# cec-wifi-bridge-rev-a.net
KiCad netlist of a schematic drawn in EAGLE
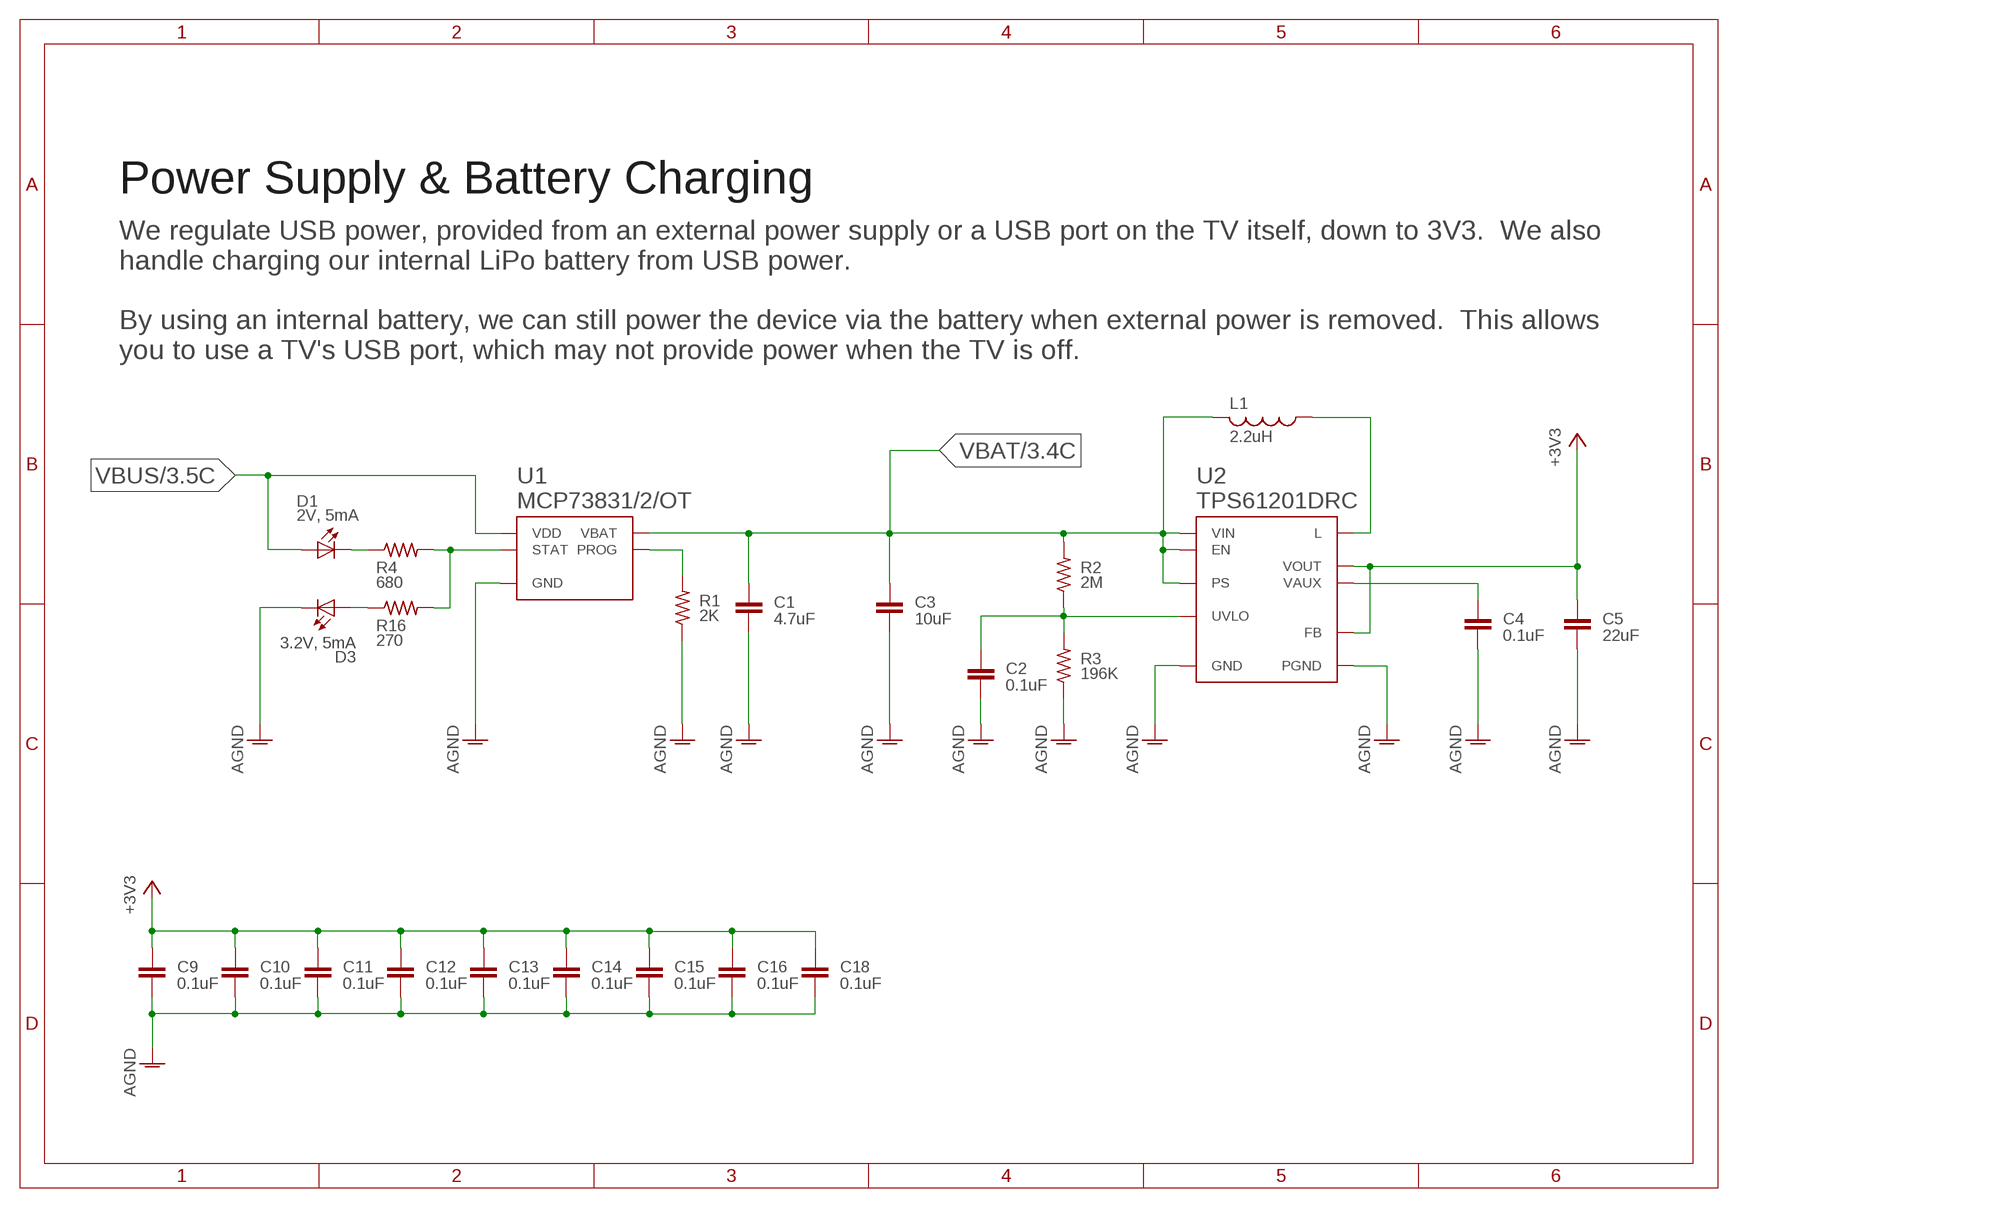
[diagram p0: schematic, sheet 1]
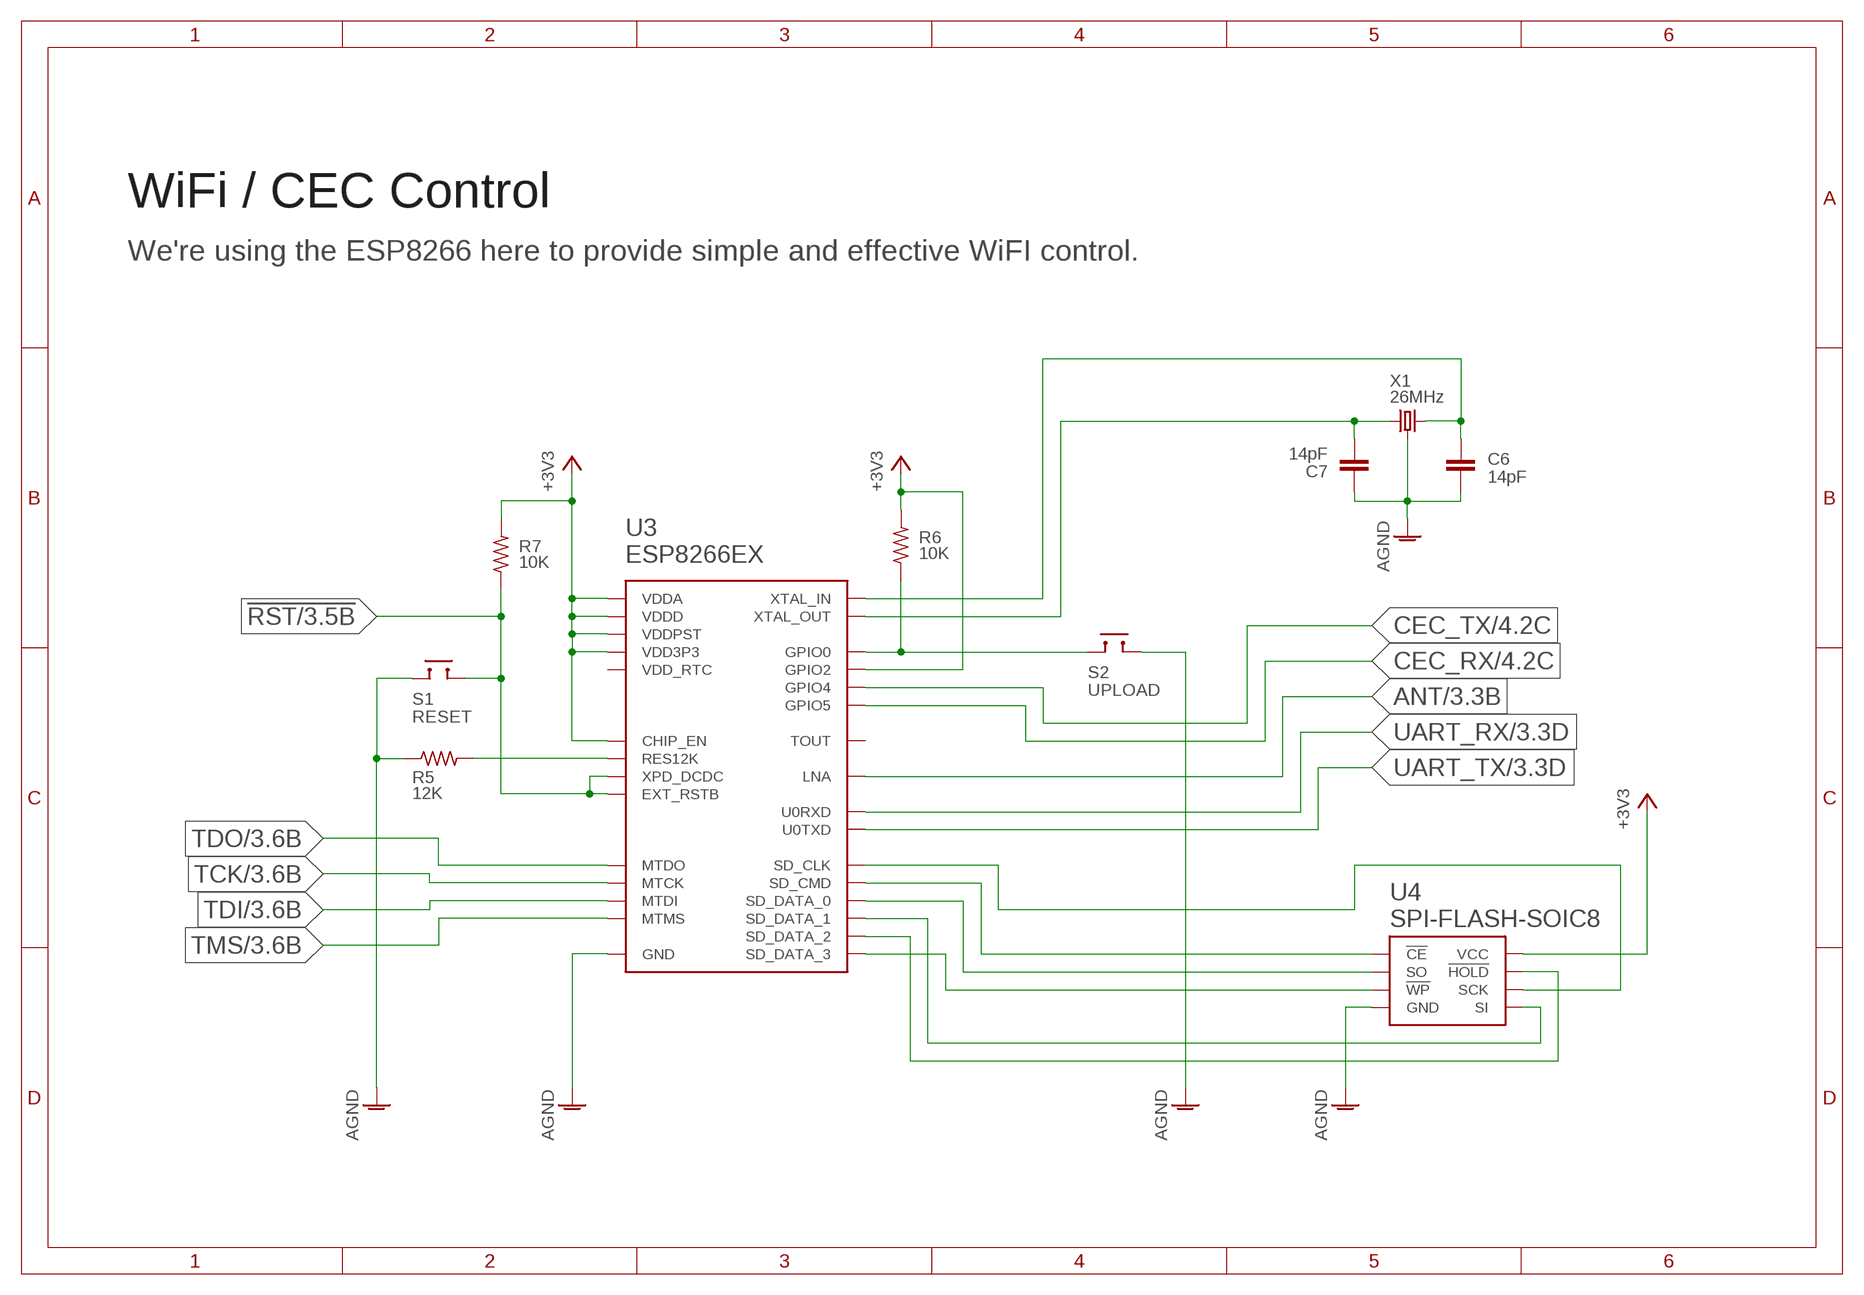
[diagram p1: schematic, sheet 2]
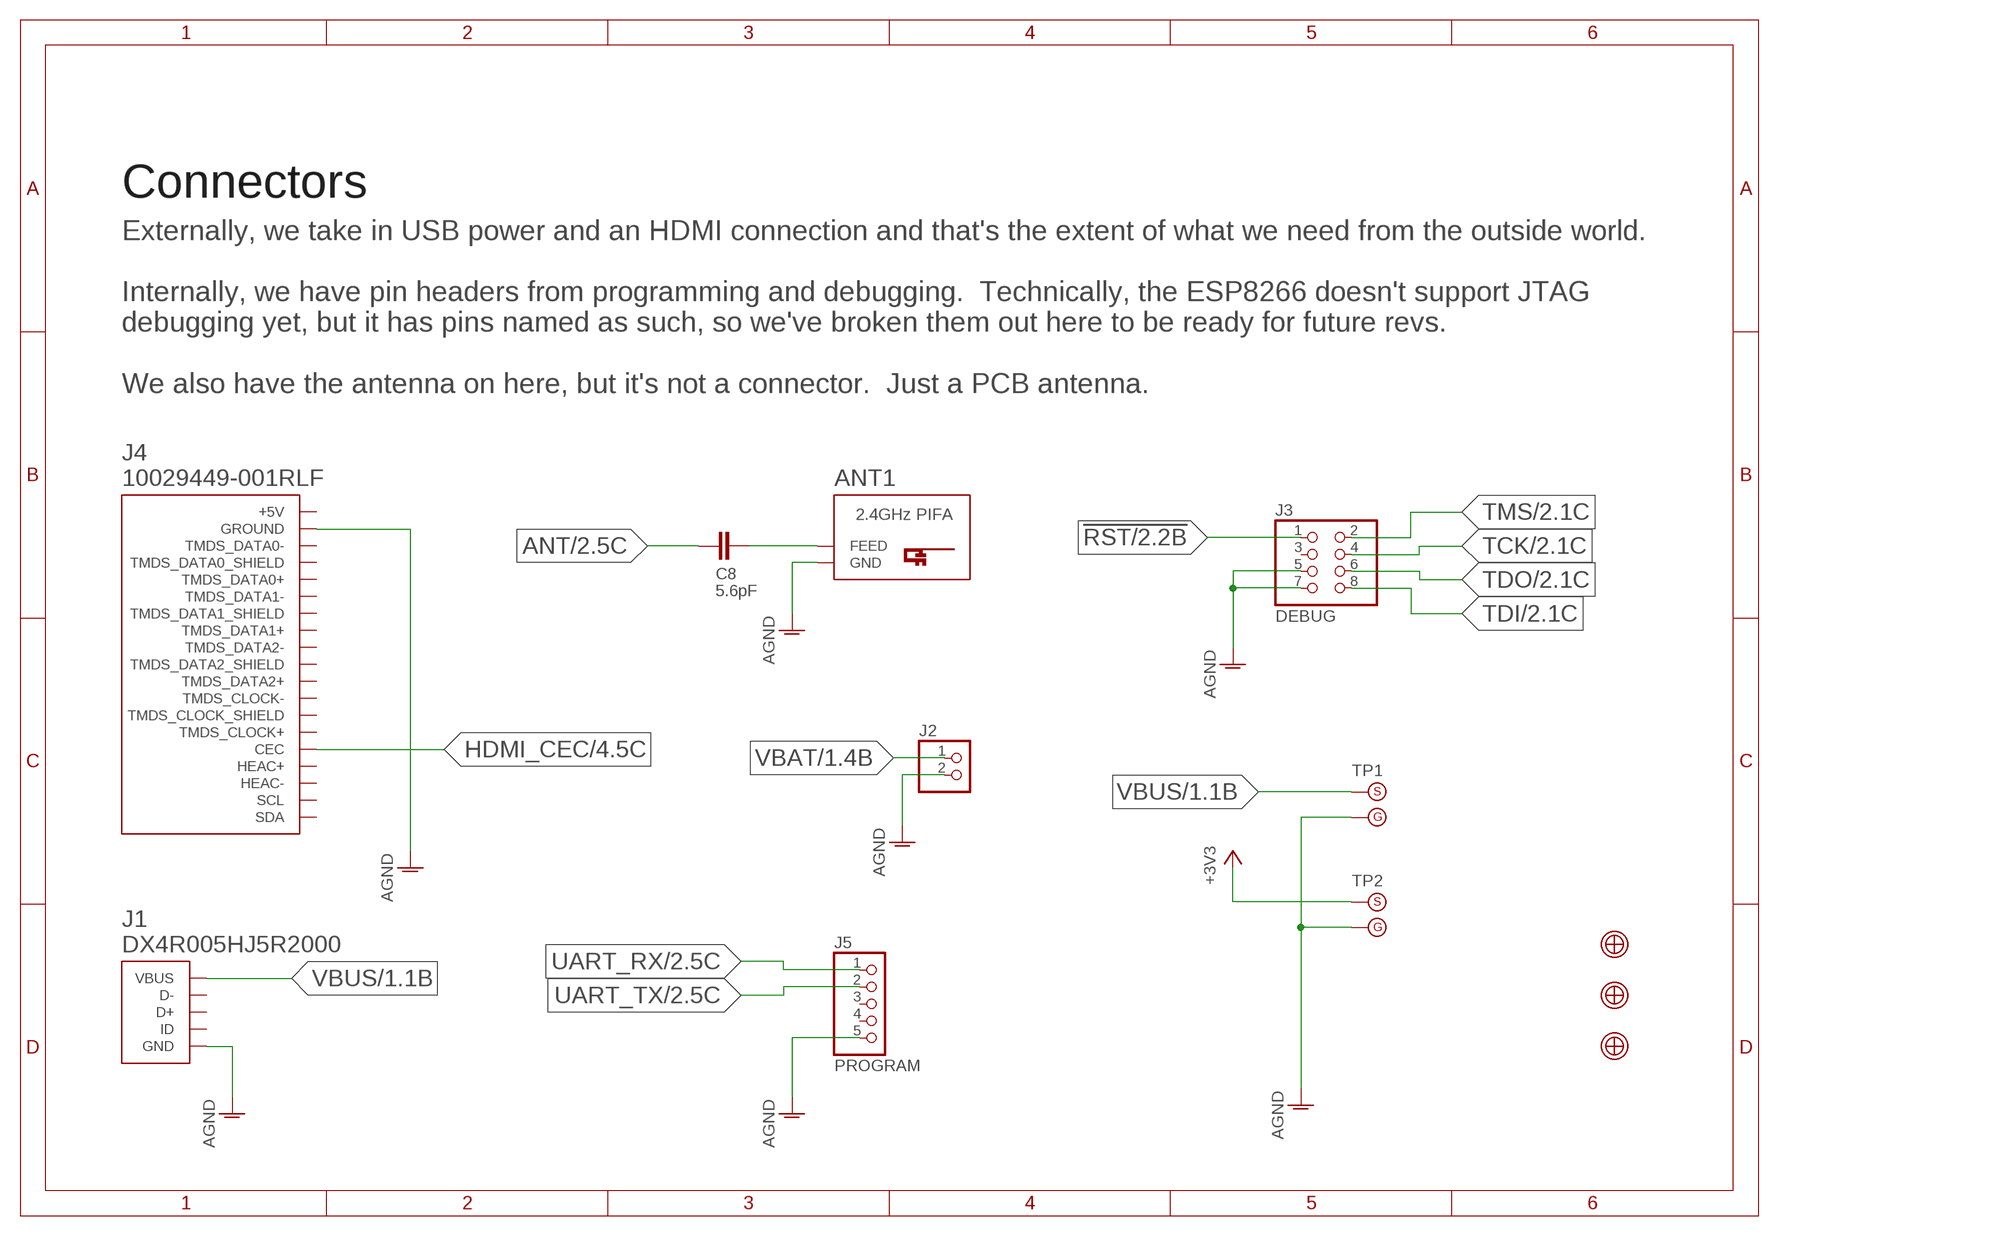
[diagram p2: schematic, sheet 3]
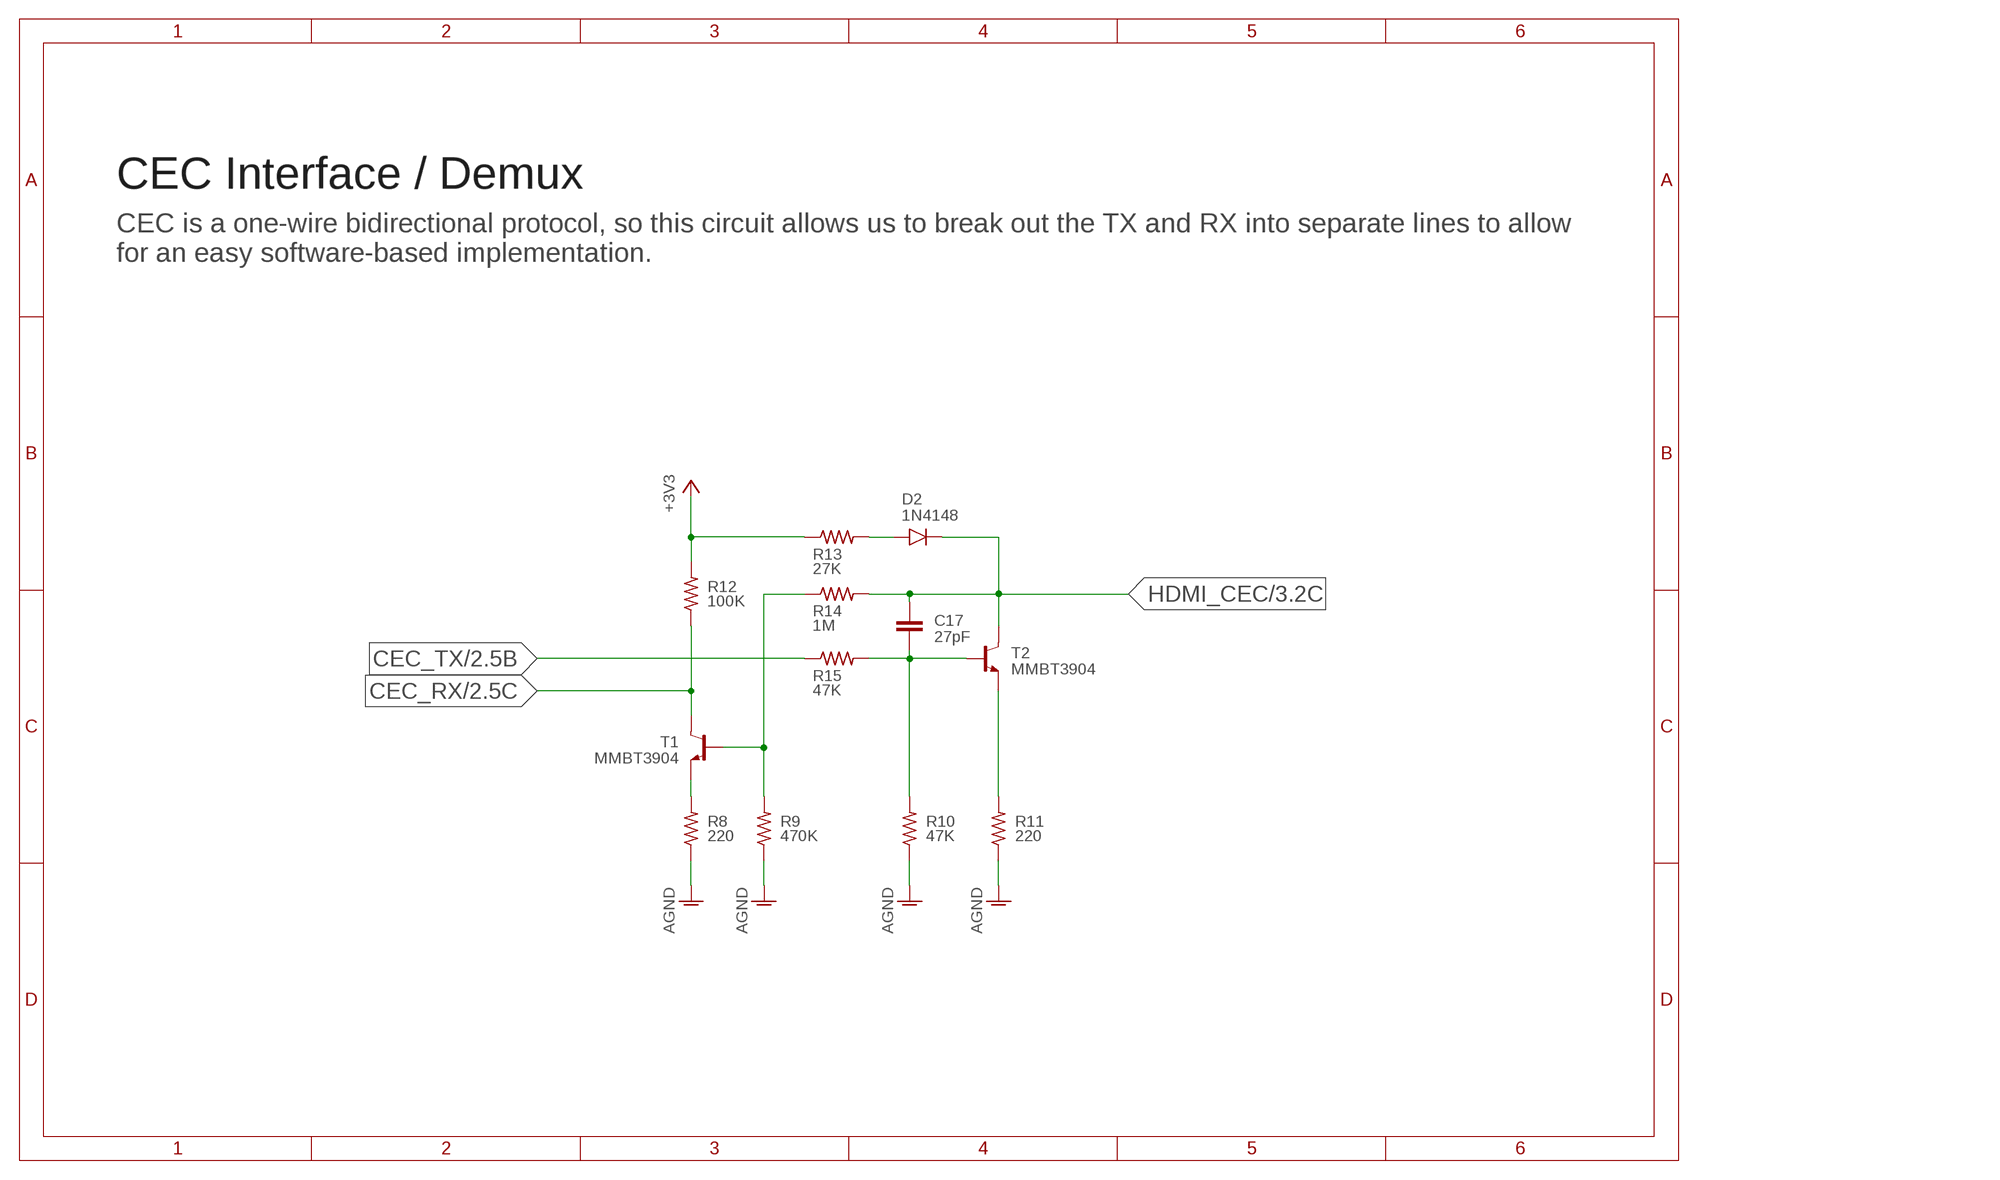
[diagram p3: schematic, sheet 4]

(export (version "E")
  (design (tool "Eeschema 10.0.6"))
  (components
    (comp (ref "C1")
      (value "4.7uF")
      (footprint "eagle-import:C0603")
      (libsource (lib "eagle-import") (part "CAPACITOR-0603"))
    )
    (comp (ref "C2")
      (value "0.1uF")
      (footprint "eagle-import:C0402")
      (libsource (lib "eagle-import") (part "CAPACITOR-0402"))
    )
    (comp (ref "C3")
      (value "10uF")
      (footprint "eagle-import:C0805")
      (libsource (lib "eagle-import") (part "CAPACITOR-0805"))
    )
    (comp (ref "C4")
      (value "0.1uF")
      (footprint "eagle-import:C0402")
      (libsource (lib "eagle-import") (part "CAPACITOR-0402"))
    )
    (comp (ref "C5")
      (value "22uF")
      (footprint "eagle-import:C0805")
      (libsource (lib "eagle-import") (part "CAPACITOR-0805"))
    )
    (comp (ref "C9")
      (value "0.1uF")
      (footprint "eagle-import:C0402")
      (libsource (lib "eagle-import") (part "CAPACITOR-0402"))
    )
    (comp (ref "C10")
      (value "0.1uF")
      (footprint "eagle-import:C0402")
      (libsource (lib "eagle-import") (part "CAPACITOR-0402"))
    )
    (comp (ref "C11")
      (value "0.1uF")
      (footprint "eagle-import:C0402")
      (libsource (lib "eagle-import") (part "CAPACITOR-0402"))
    )
    (comp (ref "C12")
      (value "0.1uF")
      (footprint "eagle-import:C0402")
      (libsource (lib "eagle-import") (part "CAPACITOR-0402"))
    )
    (comp (ref "C13")
      (value "0.1uF")
      (footprint "eagle-import:C0402")
      (libsource (lib "eagle-import") (part "CAPACITOR-0402"))
    )
    (comp (ref "C14")
      (value "0.1uF")
      (footprint "eagle-import:C0402")
      (libsource (lib "eagle-import") (part "CAPACITOR-0402"))
    )
    (comp (ref "C15")
      (value "0.1uF")
      (footprint "eagle-import:C0402")
      (libsource (lib "eagle-import") (part "CAPACITOR-0402"))
    )
    (comp (ref "C16")
      (value "0.1uF")
      (footprint "eagle-import:C0402")
      (libsource (lib "eagle-import") (part "CAPACITOR-0402"))
    )
    (comp (ref "C18")
      (value "0.1uF")
      (footprint "eagle-import:C0402")
      (libsource (lib "eagle-import") (part "CAPACITOR-0402"))
    )
    (comp (ref "D1")
      (value "2V, 5mA")
      (footprint "eagle-import:DIALIGHT-0603")
      (libsource (lib "eagle-import") (part "DIALIGHT-598-MICROSMD-0603"))
    )
    (comp (ref "D3")
      (value "3.2V, 5mA")
      (footprint "eagle-import:DIALIGHT-0603")
      (libsource (lib "eagle-import") (part "DIALIGHT-598-MICROSMD-0603"))
    )
    (comp (ref "L1")
      (value "2.2uH")
      (footprint "eagle-import:COILCRAFT-XPL2010")
      (libsource (lib "eagle-import") (part "INDUCTOR-HORIZONTAL-XPL2010"))
    )
    (comp (ref "R1")
      (value "2K")
      (footprint "eagle-import:R0402")
      (libsource (lib "eagle-import") (part "RESISTOR-0402"))
    )
    (comp (ref "R2")
      (value "2M")
      (footprint "eagle-import:R0402")
      (libsource (lib "eagle-import") (part "RESISTOR-0402"))
    )
    (comp (ref "R3")
      (value "196K")
      (footprint "eagle-import:R0402")
      (libsource (lib "eagle-import") (part "RESISTOR-0402"))
    )
    (comp (ref "R4")
      (value "680")
      (footprint "eagle-import:R0603")
      (libsource (lib "eagle-import") (part "RESISTOR-HORIZONTAL-0603"))
    )
    (comp (ref "R16")
      (value "270")
      (footprint "eagle-import:R0603")
      (libsource (lib "eagle-import") (part "RESISTOR-HORIZONTAL-0603"))
    )
    (comp (ref "U1")
      (value "MCP73831/2/OT")
      (footprint "eagle-import:5-SOT23")
      (libsource (lib "eagle-import") (part "MCP73831/2/OT"))
    )
    (comp (ref "U2")
      (value "TPS61201DRC")
      (footprint "eagle-import:S-PVSON-N10-DRC")
      (libsource (lib "eagle-import") (part "TPS61200DRC"))
    )
    (comp (ref "C17")
      (value "27pF")
      (footprint "eagle-import:C0402")
      (libsource (lib "eagle-import") (part "CAPACITOR-0402"))
    )
    (comp (ref "D2")
      (value "1N4148")
      (footprint "eagle-import:SOD123")
      (libsource (lib "eagle-import") (part "DIODE-SOD123"))
    )
    (comp (ref "R8")
      (value "220")
      (footprint "eagle-import:R0402")
      (libsource (lib "eagle-import") (part "RESISTOR-0402"))
    )
    (comp (ref "R9")
      (value "470K")
      (footprint "eagle-import:R0402")
      (libsource (lib "eagle-import") (part "RESISTOR-0402"))
    )
    (comp (ref "R10")
      (value "47K")
      (footprint "eagle-import:R0402")
      (libsource (lib "eagle-import") (part "RESISTOR-0402"))
    )
    (comp (ref "R11")
      (value "220")
      (footprint "eagle-import:R0402")
      (libsource (lib "eagle-import") (part "RESISTOR-0402"))
    )
    (comp (ref "R12")
      (value "100K")
      (footprint "eagle-import:R0402")
      (libsource (lib "eagle-import") (part "RESISTOR-0402"))
    )
    (comp (ref "R13")
      (value "27K")
      (footprint "eagle-import:R0402")
      (libsource (lib "eagle-import") (part "RESISTOR-HORIZONTAL-0402"))
    )
    (comp (ref "R14")
      (value "1M")
      (footprint "eagle-import:R0402")
      (libsource (lib "eagle-import") (part "RESISTOR-HORIZONTAL-0402"))
    )
    (comp (ref "R15")
      (value "47K")
      (footprint "eagle-import:R0402")
      (libsource (lib "eagle-import") (part "RESISTOR-HORIZONTAL-0402"))
    )
    (comp (ref "T1")
      (value "MMBT3904")
      (footprint "eagle-import:SOT-23")
      (libsource (lib "eagle-import") (part "BJT-NPN-SOT-23"))
    )
    (comp (ref "T2")
      (value "MMBT3904")
      (footprint "eagle-import:SOT-23")
      (libsource (lib "eagle-import") (part "BJT-NPN-SOT-23"))
    )
    (comp (ref "ANT1")
      (value "INVERTED_F_ANTENNA+0")
      (footprint "eagle-import:DN007+0")
      (libsource (lib "eagle-import") (part "INVERTED_F_ANTENNA+0"))
    )
    (comp (ref "C8")
      (value "5.6pF")
      (footprint "eagle-import:C0402")
      (libsource (lib "eagle-import") (part "CAPACITOR-HORIZONTAL-0402"))
    )
    (comp (ref "J1")
      (value "DX4R005HJ5R2000")
      (footprint "eagle-import:DX4R005HJ5R2000")
      (libsource (lib "eagle-import") (part "DX4R005HJ5R2000"))
    )
    (comp (ref "J2")
      (value "PINHD-1X2")
      (footprint "eagle-import:1X02")
      (libsource (lib "eagle-import") (part "PINHD-1X2"))
    )
    (comp (ref "J3")
      (value "DEBUG")
      (footprint "eagle-import:2X04")
      (libsource (lib "eagle-import") (part "PINHD-2X4"))
    )
    (comp (ref "J4")
      (value "10029449-001RLF")
      (footprint "eagle-import:10029449")
      (libsource (lib "eagle-import") (part "10029449-001RLF"))
    )
    (comp (ref "J5")
      (value "PROGRAM")
      (footprint "eagle-import:1X05")
      (libsource (lib "eagle-import") (part "PINHD-1X5"))
    )
    (comp (ref "TP1")
      (value "TESTPOINT-WITH-GND")
      (footprint "eagle-import:TESTPOINT-1.5-WITH-GND")
      (libsource (lib "eagle-import") (part "TESTPOINT-WITH-GND"))
    )
    (comp (ref "TP2")
      (value "TESTPOINT-WITH-GND")
      (footprint "eagle-import:TESTPOINT-1.5-WITH-GND")
      (libsource (lib "eagle-import") (part "TESTPOINT-WITH-GND"))
    )
    (comp (ref "U$1")
      (value "FIDUCIAL-1MM")
      (footprint "eagle-import:FIDUCIAL_1MM")
      (libsource (lib "eagle-import") (part "FIDUCIAL-1MM"))
    )
    (comp (ref "U$2")
      (value "FIDUCIAL-1MM")
      (footprint "eagle-import:FIDUCIAL_1MM")
      (libsource (lib "eagle-import") (part "FIDUCIAL-1MM"))
    )
    (comp (ref "U$3")
      (value "FIDUCIAL-1MM")
      (footprint "eagle-import:FIDUCIAL_1MM")
      (libsource (lib "eagle-import") (part "FIDUCIAL-1MM"))
    )
    (comp (ref "C6")
      (value "14pF")
      (footprint "eagle-import:C0402")
      (libsource (lib "eagle-import") (part "CAPACITOR-0402"))
    )
    (comp (ref "C7")
      (value "14pF")
      (footprint "eagle-import:C0402")
      (libsource (lib "eagle-import") (part "CAPACITOR-0402"))
    )
    (comp (ref "R5")
      (value "12K")
      (footprint "eagle-import:R0402")
      (libsource (lib "eagle-import") (part "RESISTOR-HORIZONTAL-0402"))
    )
    (comp (ref "R6")
      (value "10K")
      (footprint "eagle-import:R0402")
      (libsource (lib "eagle-import") (part "RESISTOR-0402"))
    )
    (comp (ref "R7")
      (value "10K")
      (footprint "eagle-import:R0402")
      (libsource (lib "eagle-import") (part "RESISTOR-0402"))
    )
    (comp (ref "S1")
      (value "RESET")
      (footprint "eagle-import:ALPS-SKQG")
      (libsource (lib "eagle-import") (part "MOMENTARY-ALPS-SKQG"))
    )
    (comp (ref "S2")
      (value "UPLOAD")
      (footprint "eagle-import:ALPS-SKQG")
      (libsource (lib "eagle-import") (part "MOMENTARY-ALPS-SKQG"))
    )
    (comp (ref "U3")
      (value "ESP8266EX")
      (footprint "eagle-import:ESP8266EX")
      (libsource (lib "eagle-import") (part "ESP8266EX"))
    )
    (comp (ref "U4")
      (value "SPI-FLASH-SOIC8")
      (footprint "eagle-import:SOIC-8")
      (libsource (lib "eagle-import") (part "SPI-FLASH-SOIC8"))
    )
    (comp (ref "X1")
      (value "26MHz")
      (footprint "eagle-import:EPSON-TSX-3225")
      (libsource (lib "eagle-import") (part "GROUNDED-CRYSTAL-EPSON-TSX-3225"))
    )
  )
  (nets
    (net (code "1") (name "+3V3") (class "Default")
      (node (ref "C10") (pin "1") (pinfunction "1_1") (pintype "passive"))
      (node (ref "C11") (pin "1") (pinfunction "1_1") (pintype "passive"))
      (node (ref "C12") (pin "1") (pinfunction "1_1") (pintype "passive"))
      (node (ref "C13") (pin "1") (pinfunction "1_1") (pintype "passive"))
      (node (ref "C14") (pin "1") (pinfunction "1_1") (pintype "passive"))
      (node (ref "C15") (pin "1") (pinfunction "1_1") (pintype "passive"))
      (node (ref "C16") (pin "1") (pinfunction "1_1") (pintype "passive"))
      (node (ref "C18") (pin "1") (pinfunction "1_1") (pintype "passive"))
      (node (ref "C5") (pin "1") (pinfunction "1_1") (pintype "passive"))
      (node (ref "C9") (pin "1") (pinfunction "1_1") (pintype "passive"))
      (node (ref "R12") (pin "2") (pinfunction "2_2") (pintype "passive"))
      (node (ref "R13") (pin "1") (pinfunction "1_1") (pintype "passive"))
      (node (ref "R6") (pin "2") (pinfunction "2_2") (pintype "passive"))
      (node (ref "R7") (pin "2") (pinfunction "2_2") (pintype "passive"))
      (node (ref "TP2") (pin "S") (pinfunction "S_S") (pintype "bidirectional"))
      (node (ref "U2") (pin "P$10") (pinfunction "FB_P$10") (pintype "bidirectional"))
      (node (ref "U2") (pin "P$2") (pinfunction "VOUT_P$2") (pintype "bidirectional"))
      (node (ref "U3") (pin "CHIP_EN") (pinfunction "CHIP_EN_CHIP_EN") (pintype "bidirectional"))
      (node (ref "U3") (pin "GPIO2") (pinfunction "GPIO2_GPIO2") (pintype "bidirectional"))
      (node (ref "U3") (pin "VDD3P3") (pinfunction "VDD3P3_VDD3P3") (pintype "bidirectional"))
      (node (ref "U3") (pin "VDD3P3$2") (pinfunction "VDD3P3_VDD3P3$2") (pintype "bidirectional"))
      (node (ref "U3") (pin "VDDA") (pinfunction "VDDA_VDDA") (pintype "bidirectional"))
      (node (ref "U3") (pin "VDDA$2") (pinfunction "VDDA_VDDA$2") (pintype "bidirectional"))
      (node (ref "U3") (pin "VDDD") (pinfunction "VDDD_VDDD") (pintype "bidirectional"))
      (node (ref "U3") (pin "VDDPST") (pinfunction "VDDPST_VDDPST") (pintype "bidirectional"))
      (node (ref "U3") (pin "VDDPST$2") (pinfunction "VDDPST_VDDPST$2") (pintype "bidirectional"))
      (node (ref "U4") (pin "P$8") (pinfunction "VCC_P$8") (pintype "bidirectional"))
    )
    (net (code "2") (name "AGND") (class "Default")
      (node (ref "ANT1") (pin "GND") (pinfunction "GND_GND") (pintype "bidirectional"))
      (node (ref "ANT1") (pin "GND@1") (pinfunction "GND_GND@1") (pintype "bidirectional"))
      (node (ref "C1") (pin "2") (pinfunction "2_2") (pintype "passive"))
      (node (ref "C10") (pin "2") (pinfunction "2_2") (pintype "passive"))
      (node (ref "C11") (pin "2") (pinfunction "2_2") (pintype "passive"))
      (node (ref "C12") (pin "2") (pinfunction "2_2") (pintype "passive"))
      (node (ref "C13") (pin "2") (pinfunction "2_2") (pintype "passive"))
      (node (ref "C14") (pin "2") (pinfunction "2_2") (pintype "passive"))
      (node (ref "C15") (pin "2") (pinfunction "2_2") (pintype "passive"))
      (node (ref "C16") (pin "2") (pinfunction "2_2") (pintype "passive"))
      (node (ref "C18") (pin "2") (pinfunction "2_2") (pintype "passive"))
      (node (ref "C2") (pin "2") (pinfunction "2_2") (pintype "passive"))
      (node (ref "C3") (pin "2") (pinfunction "2_2") (pintype "passive"))
      (node (ref "C4") (pin "2") (pinfunction "2_2") (pintype "passive"))
      (node (ref "C5") (pin "2") (pinfunction "2_2") (pintype "passive"))
      (node (ref "C6") (pin "2") (pinfunction "2_2") (pintype "passive"))
      (node (ref "C7") (pin "1") (pinfunction "1_1") (pintype "passive"))
      (node (ref "C9") (pin "2") (pinfunction "2_2") (pintype "passive"))
      (node (ref "D3") (pin "2") (pinfunction "C_2") (pintype "passive"))
      (node (ref "J1") (pin "5") (pinfunction "GND_5") (pintype "bidirectional"))
      (node (ref "J1") (pin "CASE_1") (pinfunction "GND_CASE_1") (pintype "bidirectional"))
      (node (ref "J1") (pin "CASE_2") (pinfunction "GND_CASE_2") (pintype "bidirectional"))
      (node (ref "J1") (pin "CASE_3") (pinfunction "GND_CASE_3") (pintype "bidirectional"))
      (node (ref "J1") (pin "CASE_4") (pinfunction "GND_CASE_4") (pintype "bidirectional"))
      (node (ref "J2") (pin "2") (pinfunction "2_2") (pintype "passive"))
      (node (ref "J3") (pin "5") (pinfunction "5_5") (pintype "passive"))
      (node (ref "J3") (pin "7") (pinfunction "7_7") (pintype "passive"))
      (node (ref "J4") (pin "P$17") (pinfunction "GROUND_P$17") (pintype "bidirectional"))
      (node (ref "J5") (pin "5") (pinfunction "5_5") (pintype "passive"))
      (node (ref "R1") (pin "1") (pinfunction "1_1") (pintype "passive"))
      (node (ref "R10") (pin "1") (pinfunction "1_1") (pintype "passive"))
      (node (ref "R11") (pin "1") (pinfunction "1_1") (pintype "passive"))
      (node (ref "R3") (pin "1") (pinfunction "1_1") (pintype "passive"))
      (node (ref "R5") (pin "1") (pinfunction "1_1") (pintype "passive"))
      (node (ref "R8") (pin "1") (pinfunction "1_1") (pintype "passive"))
      (node (ref "R9") (pin "1") (pinfunction "1_1") (pintype "passive"))
      (node (ref "S1") (pin "P$1") (pinfunction "P$1_P$1") (pintype "bidirectional"))
      (node (ref "S1") (pin "P$2") (pinfunction "P$1_P$2") (pintype "bidirectional"))
      (node (ref "S2") (pin "P$3") (pinfunction "P$2_P$3") (pintype "bidirectional"))
      (node (ref "S2") (pin "P$4") (pinfunction "P$2_P$4") (pintype "bidirectional"))
      (node (ref "TP1") (pin "G") (pinfunction "G_G") (pintype "bidirectional"))
      (node (ref "TP2") (pin "G") (pinfunction "G_G") (pintype "bidirectional"))
      (node (ref "U1") (pin "2") (pinfunction "GND_2") (pintype "bidirectional"))
      (node (ref "U2") (pin "GND-VIA-1") (pinfunction "PGND_GND-VIA-1") (pintype "bidirectional"))
      (node (ref "U2") (pin "GND-VIA-2") (pinfunction "PGND_GND-VIA-2") (pintype "bidirectional"))
      (node (ref "U2") (pin "GND-VIA-3") (pinfunction "PGND_GND-VIA-3") (pintype "bidirectional"))
      (node (ref "U2") (pin "GND-VIA-4") (pinfunction "PGND_GND-VIA-4") (pintype "bidirectional"))
      (node (ref "U2") (pin "GND-VIA-5") (pinfunction "PGND_GND-VIA-5") (pintype "bidirectional"))
      (node (ref "U2") (pin "P$4") (pinfunction "PGND_P$4") (pintype "bidirectional"))
      (node (ref "U2") (pin "P$9") (pinfunction "GND_P$9") (pintype "bidirectional"))
      (node (ref "U2") (pin "THERMAL") (pinfunction "PGND_THERMAL") (pintype "bidirectional"))
      (node (ref "U2") (pin "THERMAL1") (pinfunction "PGND_THERMAL1") (pintype "bidirectional"))
      (node (ref "U2") (pin "THERMAL2") (pinfunction "PGND_THERMAL2") (pintype "bidirectional"))
      (node (ref "U2") (pin "THERMAL3") (pinfunction "PGND_THERMAL3") (pintype "bidirectional"))
      (node (ref "U2") (pin "THERMAL4") (pinfunction "PGND_THERMAL4") (pintype "bidirectional"))
      (node (ref "U3") (pin "GND") (pinfunction "GND_GND") (pintype "bidirectional"))
      (node (ref "U3") (pin "P$1") (pinfunction "GND_P$1") (pintype "bidirectional"))
      (node (ref "U3") (pin "P$2") (pinfunction "GND_P$2") (pintype "bidirectional"))
      (node (ref "U3") (pin "P$3") (pinfunction "GND_P$3") (pintype "bidirectional"))
      (node (ref "U3") (pin "P$4") (pinfunction "GND_P$4") (pintype "bidirectional"))
      (node (ref "U3") (pin "P$5") (pinfunction "GND_P$5") (pintype "bidirectional"))
      (node (ref "U3") (pin "P$6") (pinfunction "GND_P$6") (pintype "bidirectional"))
      (node (ref "U3") (pin "P$7") (pinfunction "GND_P$7") (pintype "bidirectional"))
      (node (ref "U3") (pin "P$8") (pinfunction "GND_P$8") (pintype "bidirectional"))
      (node (ref "U3") (pin "P$9") (pinfunction "GND_P$9") (pintype "bidirectional"))
      (node (ref "U4") (pin "P$4") (pinfunction "GND_P$4") (pintype "bidirectional"))
      (node (ref "X1") (pin "P$2") (pinfunction "GND_P$2") (pintype "passive"))
      (node (ref "X1") (pin "P$4") (pinfunction "GND_P$4") (pintype "passive"))
    )
    (net (code "3") (name "ANT") (class "Default")
      (node (ref "C8") (pin "1") (pinfunction "1_1") (pintype "passive"))
      (node (ref "U3") (pin "LNA") (pinfunction "LNA_LNA") (pintype "bidirectional"))
    )
    (net (code "4") (name "CEC_RX") (class "Default")
      (node (ref "R12") (pin "1") (pinfunction "1_1") (pintype "passive"))
      (node (ref "T1") (pin "P$3") (pinfunction "C_P$3") (pintype "bidirectional"))
      (node (ref "U3") (pin "GPOIO5") (pinfunction "GPIO5_GPOIO5") (pintype "bidirectional"))
    )
    (net (code "5") (name "CEC_TX") (class "Default")
      (node (ref "R15") (pin "1") (pinfunction "1_1") (pintype "passive"))
      (node (ref "U3") (pin "GPIO4") (pinfunction "GPIO4_GPIO4") (pintype "bidirectional"))
    )
    (net (code "6") (name "HDMI_CEC") (class "Default")
      (node (ref "C17") (pin "1") (pinfunction "1_1") (pintype "passive"))
      (node (ref "D2") (pin "C") (pinfunction "C_C") (pintype "passive"))
      (node (ref "J4") (pin "P$13") (pinfunction "CEC_P$13") (pintype "bidirectional"))
      (node (ref "R14") (pin "2") (pinfunction "2_2") (pintype "passive"))
      (node (ref "T2") (pin "P$3") (pinfunction "C_P$3") (pintype "bidirectional"))
    )
    (net (code "7") (name "Net-(ANT1-PadFEED)") (class "Default")
      (node (ref "ANT1") (pin "FEED") (pinfunction "FEED_FEED") (pintype "bidirectional"))
      (node (ref "C8") (pin "2") (pinfunction "2_2") (pintype "passive"))
    )
    (net (code "8") (name "Net-(D1-C)") (class "Default")
      (node (ref "D1") (pin "2") (pinfunction "C_2") (pintype "passive"))
      (node (ref "R4") (pin "1") (pinfunction "1_1") (pintype "passive"))
    )
    (net (code "9") (name "Net-(D2-PadA)") (class "Default")
      (node (ref "D2") (pin "A") (pinfunction "A_A") (pintype "passive"))
      (node (ref "R13") (pin "2") (pinfunction "2_2") (pintype "passive"))
    )
    (net (code "10") (name "Net-(D3-A)") (class "Default")
      (node (ref "D3") (pin "1") (pinfunction "A_1") (pintype "passive"))
      (node (ref "R16") (pin "1") (pinfunction "1_1") (pintype "passive"))
    )
    (net (code "11") (name "Net-(L1-1)") (class "Default")
      (node (ref "L1") (pin "P$1") (pinfunction "1_P$1") (pintype "passive"))
      (node (ref "U2") (pin "P$3") (pinfunction "L_P$3") (pintype "bidirectional"))
    )
    (net (code "12") (name "Net-(R5-Pad2)") (class "Default")
      (node (ref "R5") (pin "2") (pinfunction "2_2") (pintype "passive"))
      (node (ref "U3") (pin "RES12K") (pinfunction "RES12K_RES12K") (pintype "bidirectional"))
    )
    (net (code "13") (name "Net-(R6-Pad1)") (class "Default")
      (node (ref "R6") (pin "1") (pinfunction "1_1") (pintype "passive"))
      (node (ref "S2") (pin "P$1") (pinfunction "P$1_P$1") (pintype "bidirectional"))
      (node (ref "S2") (pin "P$2") (pinfunction "P$1_P$2") (pintype "bidirectional"))
      (node (ref "U3") (pin "GPIO0") (pinfunction "GPIO0_GPIO0") (pintype "bidirectional"))
    )
    (net (code "14") (name "Net-(T1-B)") (class "Default")
      (node (ref "R14") (pin "1") (pinfunction "1_1") (pintype "passive"))
      (node (ref "R9") (pin "2") (pinfunction "2_2") (pintype "passive"))
      (node (ref "T1") (pin "P$1") (pinfunction "B_P$1") (pintype "bidirectional"))
    )
    (net (code "15") (name "Net-(T1-E)") (class "Default")
      (node (ref "R8") (pin "2") (pinfunction "2_2") (pintype "passive"))
      (node (ref "T1") (pin "P$2") (pinfunction "E_P$2") (pintype "bidirectional"))
    )
    (net (code "16") (name "Net-(T2-B)") (class "Default")
      (node (ref "C17") (pin "2") (pinfunction "2_2") (pintype "passive"))
      (node (ref "R10") (pin "2") (pinfunction "2_2") (pintype "passive"))
      (node (ref "R15") (pin "2") (pinfunction "2_2") (pintype "passive"))
      (node (ref "T2") (pin "P$1") (pinfunction "B_P$1") (pintype "bidirectional"))
    )
    (net (code "17") (name "Net-(T2-E)") (class "Default")
      (node (ref "R11") (pin "2") (pinfunction "2_2") (pintype "passive"))
      (node (ref "T2") (pin "P$2") (pinfunction "E_P$2") (pintype "bidirectional"))
    )
    (net (code "18") (name "Net-(U1-PROG)") (class "Default")
      (node (ref "R1") (pin "2") (pinfunction "2_2") (pintype "passive"))
      (node (ref "U1") (pin "5") (pinfunction "PROG_5") (pintype "bidirectional"))
    )
    (net (code "19") (name "Net-(U1-STAT)") (class "Default")
      (node (ref "R16") (pin "2") (pinfunction "2_2") (pintype "passive"))
      (node (ref "R4") (pin "2") (pinfunction "2_2") (pintype "passive"))
      (node (ref "U1") (pin "1") (pinfunction "STAT_1") (pintype "bidirectional"))
    )
    (net (code "20") (name "Net-(U2-UVLO)") (class "Default")
      (node (ref "C2") (pin "1") (pinfunction "1_1") (pintype "passive"))
      (node (ref "R2") (pin "1") (pinfunction "1_1") (pintype "passive"))
      (node (ref "R3") (pin "2") (pinfunction "2_2") (pintype "passive"))
      (node (ref "U2") (pin "P$7") (pinfunction "UVLO_P$7") (pintype "bidirectional"))
    )
    (net (code "21") (name "Net-(U2-VAUX)") (class "Default")
      (node (ref "C4") (pin "1") (pinfunction "1_1") (pintype "passive"))
      (node (ref "U2") (pin "P$1") (pinfunction "VAUX_P$1") (pintype "bidirectional"))
    )
    (net (code "22") (name "Net-(U4-SCK)") (class "Default")
      (node (ref "U3") (pin "SD_CLK") (pinfunction "SD_CLK_SD_CLK") (pintype "bidirectional"))
      (node (ref "U4") (pin "P$6") (pinfunction "SCK_P$6") (pintype "bidirectional"))
    )
    (net (code "23") (name "Net-(U4-SI)") (class "Default")
      (node (ref "U3") (pin "SD_DATA_1") (pinfunction "SD_DATA_1_SD_DATA_1") (pintype "bidirectional"))
      (node (ref "U4") (pin "P$5") (pinfunction "SI_P$5") (pintype "bidirectional"))
    )
    (net (code "24") (name "Net-(U4-SO)") (class "Default")
      (node (ref "U3") (pin "SD_DATA_0") (pinfunction "SD_DATA_0_SD_DATA_0") (pintype "bidirectional"))
      (node (ref "U4") (pin "P$2") (pinfunction "SO_P$2") (pintype "bidirectional"))
    )
    (net (code "25") (name "Net-(U4-~{CE})") (class "Default")
      (node (ref "U3") (pin "SD_CMD") (pinfunction "SD_CMD_SD_CMD") (pintype "bidirectional"))
      (node (ref "U4") (pin "P$1") (pinfunction "~{CE}_P$1") (pintype "bidirectional"))
    )
    (net (code "26") (name "Net-(U4-~{HOLD})") (class "Default")
      (node (ref "U3") (pin "SD_DATA_2") (pinfunction "SD_DATA_2_SD_DATA_2") (pintype "bidirectional"))
      (node (ref "U4") (pin "P$7") (pinfunction "~{HOLD}_P$7") (pintype "bidirectional"))
    )
    (net (code "27") (name "Net-(U4-~{WP})") (class "Default")
      (node (ref "U3") (pin "SD_DATA_3") (pinfunction "SD_DATA_3_SD_DATA_3") (pintype "bidirectional"))
      (node (ref "U4") (pin "P$3") (pinfunction "~{WP}_P$3") (pintype "bidirectional"))
    )
    (net (code "28") (name "Net-(X1-1)") (class "Default")
      (node (ref "C7") (pin "2") (pinfunction "2_2") (pintype "passive"))
      (node (ref "U3") (pin "XTAL_OUT") (pinfunction "XTAL_OUT_XTAL_OUT") (pintype "bidirectional"))
      (node (ref "X1") (pin "P$1") (pinfunction "1_P$1") (pintype "passive"))
    )
    (net (code "29") (name "Net-(X1-2)") (class "Default")
      (node (ref "C6") (pin "1") (pinfunction "1_1") (pintype "passive"))
      (node (ref "U3") (pin "XTAL_IN") (pinfunction "XTAL_IN_XTAL_IN") (pintype "bidirectional"))
      (node (ref "X1") (pin "P$3") (pinfunction "2_P$3") (pintype "passive"))
    )
    (net (code "30") (name "TCK") (class "Default")
      (node (ref "J3") (pin "4") (pinfunction "4_4") (pintype "passive"))
      (node (ref "U3") (pin "MTCK") (pinfunction "MTCK_MTCK") (pintype "bidirectional"))
    )
    (net (code "31") (name "TDI") (class "Default")
      (node (ref "J3") (pin "8") (pinfunction "8_8") (pintype "passive"))
      (node (ref "U3") (pin "MTDI") (pinfunction "MTDI_MTDI") (pintype "bidirectional"))
    )
    (net (code "32") (name "TDO") (class "Default")
      (node (ref "J3") (pin "6") (pinfunction "6_6") (pintype "passive"))
      (node (ref "U3") (pin "MTDO") (pinfunction "MTDO_MTDO") (pintype "bidirectional"))
    )
    (net (code "33") (name "TMS") (class "Default")
      (node (ref "J3") (pin "2") (pinfunction "2_2") (pintype "passive"))
      (node (ref "U3") (pin "MTMS") (pinfunction "MTMS_MTMS") (pintype "bidirectional"))
    )
    (net (code "34") (name "UART_RX") (class "Default")
      (node (ref "J5") (pin "1") (pinfunction "1_1") (pintype "passive"))
      (node (ref "U3") (pin "U0RXD") (pinfunction "U0RXD_U0RXD") (pintype "bidirectional"))
    )
    (net (code "35") (name "UART_TX") (class "Default")
      (node (ref "J5") (pin "2") (pinfunction "2_2") (pintype "passive"))
      (node (ref "U3") (pin "U0TXD") (pinfunction "U0TXD_U0TXD") (pintype "bidirectional"))
    )
    (net (code "36") (name "VBAT") (class "Default")
      (node (ref "C1") (pin "1") (pinfunction "1_1") (pintype "passive"))
      (node (ref "C3") (pin "1") (pinfunction "1_1") (pintype "passive"))
      (node (ref "J2") (pin "1") (pinfunction "1_1") (pintype "passive"))
      (node (ref "L1") (pin "P$2") (pinfunction "2_P$2") (pintype "passive"))
      (node (ref "R2") (pin "2") (pinfunction "2_2") (pintype "passive"))
      (node (ref "U1") (pin "3") (pinfunction "VBAT_3") (pintype "bidirectional"))
      (node (ref "U2") (pin "P$5") (pinfunction "VIN_P$5") (pintype "bidirectional"))
      (node (ref "U2") (pin "P$6") (pinfunction "EN_P$6") (pintype "bidirectional"))
      (node (ref "U2") (pin "P$8") (pinfunction "PS_P$8") (pintype "bidirectional"))
    )
    (net (code "37") (name "VBUS") (class "Default")
      (node (ref "D1") (pin "1") (pinfunction "A_1") (pintype "passive"))
      (node (ref "J1") (pin "1") (pinfunction "VBUS_1") (pintype "bidirectional"))
      (node (ref "TP1") (pin "S") (pinfunction "S_S") (pintype "bidirectional"))
      (node (ref "U1") (pin "4") (pinfunction "VDD_4") (pintype "bidirectional"))
    )
    (net (code "38") (name "unconnected-(J1-D+-Pad3)") (class "Default")
      (node (ref "J1") (pin "3") (pinfunction "D+_3") (pintype "bidirectional"))
    )
    (net (code "39") (name "unconnected-(J1-D--Pad2)") (class "Default")
      (node (ref "J1") (pin "2") (pinfunction "D-_2") (pintype "bidirectional"))
    )
    (net (code "40") (name "unconnected-(J1-ID-Pad4)") (class "Default")
      (node (ref "J1") (pin "4") (pinfunction "ID_4") (pintype "bidirectional"))
    )
    (net (code "41") (name "unconnected-(J3-Pad3)") (class "Default")
      (node (ref "J3") (pin "3") (pinfunction "3_3") (pintype "passive"))
    )
    (net (code "42") (name "unconnected-(J4-+5V-PadP$18)") (class "Default")
      (node (ref "J4") (pin "P$18") (pinfunction "+5V_P$18") (pintype "bidirectional"))
    )
    (net (code "43") (name "unconnected-(J4-HEAC+-PadP$14)") (class "Default")
      (node (ref "J4") (pin "P$14") (pinfunction "HEAC+_P$14") (pintype "bidirectional"))
    )
    (net (code "44") (name "unconnected-(J4-HEAC--PadP$19)") (class "Default")
      (node (ref "J4") (pin "P$19") (pinfunction "HEAC-_P$19") (pintype "bidirectional"))
    )
    (net (code "45") (name "unconnected-(J4-SCL-PadP$15)") (class "Default")
      (node (ref "J4") (pin "P$15") (pinfunction "SCL_P$15") (pintype "bidirectional"))
    )
    (net (code "46") (name "unconnected-(J4-SDA-PadP$16)") (class "Default")
      (node (ref "J4") (pin "P$16") (pinfunction "SDA_P$16") (pintype "bidirectional"))
    )
    (net (code "47") (name "unconnected-(J4-TMDS_CLOCK+-PadP$10)") (class "Default")
      (node (ref "J4") (pin "P$10") (pinfunction "TMDS_CLOCK+_P$10") (pintype "bidirectional"))
    )
    (net (code "48") (name "unconnected-(J4-TMDS_CLOCK--PadP$12)") (class "Default")
      (node (ref "J4") (pin "P$12") (pinfunction "TMDS_CLOCK-_P$12") (pintype "bidirectional"))
    )
    (net (code "49") (name "unconnected-(J4-TMDS_CLOCK_SHIELD-PadP$11)") (class "Default")
      (node (ref "J4") (pin "P$11") (pinfunction "TMDS_CLOCK_SHIELD_P$11") (pintype "bidirectional"))
    )
    (net (code "50") (name "unconnected-(J4-TMDS_DATA0+-PadP$7)") (class "Default")
      (node (ref "J4") (pin "P$7") (pinfunction "TMDS_DATA0+_P$7") (pintype "bidirectional"))
    )
    (net (code "51") (name "unconnected-(J4-TMDS_DATA0--PadP$9)") (class "Default")
      (node (ref "J4") (pin "P$9") (pinfunction "TMDS_DATA0-_P$9") (pintype "bidirectional"))
    )
    (net (code "52") (name "unconnected-(J4-TMDS_DATA0_SHIELD-PadP$8)") (class "Default")
      (node (ref "J4") (pin "P$8") (pinfunction "TMDS_DATA0_SHIELD_P$8") (pintype "bidirectional"))
    )
    (net (code "53") (name "unconnected-(J4-TMDS_DATA1+-PadP$4)") (class "Default")
      (node (ref "J4") (pin "P$4") (pinfunction "TMDS_DATA1+_P$4") (pintype "bidirectional"))
    )
    (net (code "54") (name "unconnected-(J4-TMDS_DATA1--PadP$6)") (class "Default")
      (node (ref "J4") (pin "P$6") (pinfunction "TMDS_DATA1-_P$6") (pintype "bidirectional"))
    )
    (net (code "55") (name "unconnected-(J4-TMDS_DATA1_SHIELD-PadP$5)") (class "Default")
      (node (ref "J4") (pin "P$5") (pinfunction "TMDS_DATA1_SHIELD_P$5") (pintype "bidirectional"))
    )
    (net (code "56") (name "unconnected-(J4-TMDS_DATA2+-PadP$1)") (class "Default")
      (node (ref "J4") (pin "P$1") (pinfunction "TMDS_DATA2+_P$1") (pintype "bidirectional"))
    )
    (net (code "57") (name "unconnected-(J4-TMDS_DATA2--PadP$3)") (class "Default")
      (node (ref "J4") (pin "P$3") (pinfunction "TMDS_DATA2-_P$3") (pintype "bidirectional"))
    )
    (net (code "58") (name "unconnected-(J4-TMDS_DATA2_SHIELD-PadP$2)") (class "Default")
      (node (ref "J4") (pin "P$2") (pinfunction "TMDS_DATA2_SHIELD_P$2") (pintype "bidirectional"))
    )
    (net (code "59") (name "unconnected-(J5-Pad3)") (class "Default")
      (node (ref "J5") (pin "3") (pinfunction "3_3") (pintype "passive"))
    )
    (net (code "60") (name "unconnected-(J5-Pad4)") (class "Default")
      (node (ref "J5") (pin "4") (pinfunction "4_4") (pintype "passive"))
    )
    (net (code "61") (name "unconnected-(U3-PadTOUT)") (class "Default")
      (node (ref "U3") (pin "TOUT") (pinfunction "TOUT_TOUT") (pintype "bidirectional"))
    )
    (net (code "62") (name "unconnected-(U3-PadVDD_RTC)") (class "Default")
      (node (ref "U3") (pin "VDD_RTC") (pinfunction "VDD_RTC_VDD_RTC") (pintype "bidirectional"))
    )
    (net (code "63") (name "~{RST}") (class "Default")
      (node (ref "J3") (pin "1") (pinfunction "1_1") (pintype "passive"))
      (node (ref "R7") (pin "1") (pinfunction "1_1") (pintype "passive"))
      (node (ref "S1") (pin "P$3") (pinfunction "P$2_P$3") (pintype "bidirectional"))
      (node (ref "S1") (pin "P$4") (pinfunction "P$2_P$4") (pintype "bidirectional"))
      (node (ref "U3") (pin "EXT_RSTB") (pinfunction "EXT_RSTB_EXT_RSTB") (pintype "bidirectional"))
      (node (ref "U3") (pin "XPD_DCDC") (pinfunction "XPD_DCDC_XPD_DCDC") (pintype "bidirectional"))
    )
  )
)
